# Temp_monitor.net
KiCad netlist of a schematic drawn in EAGLE
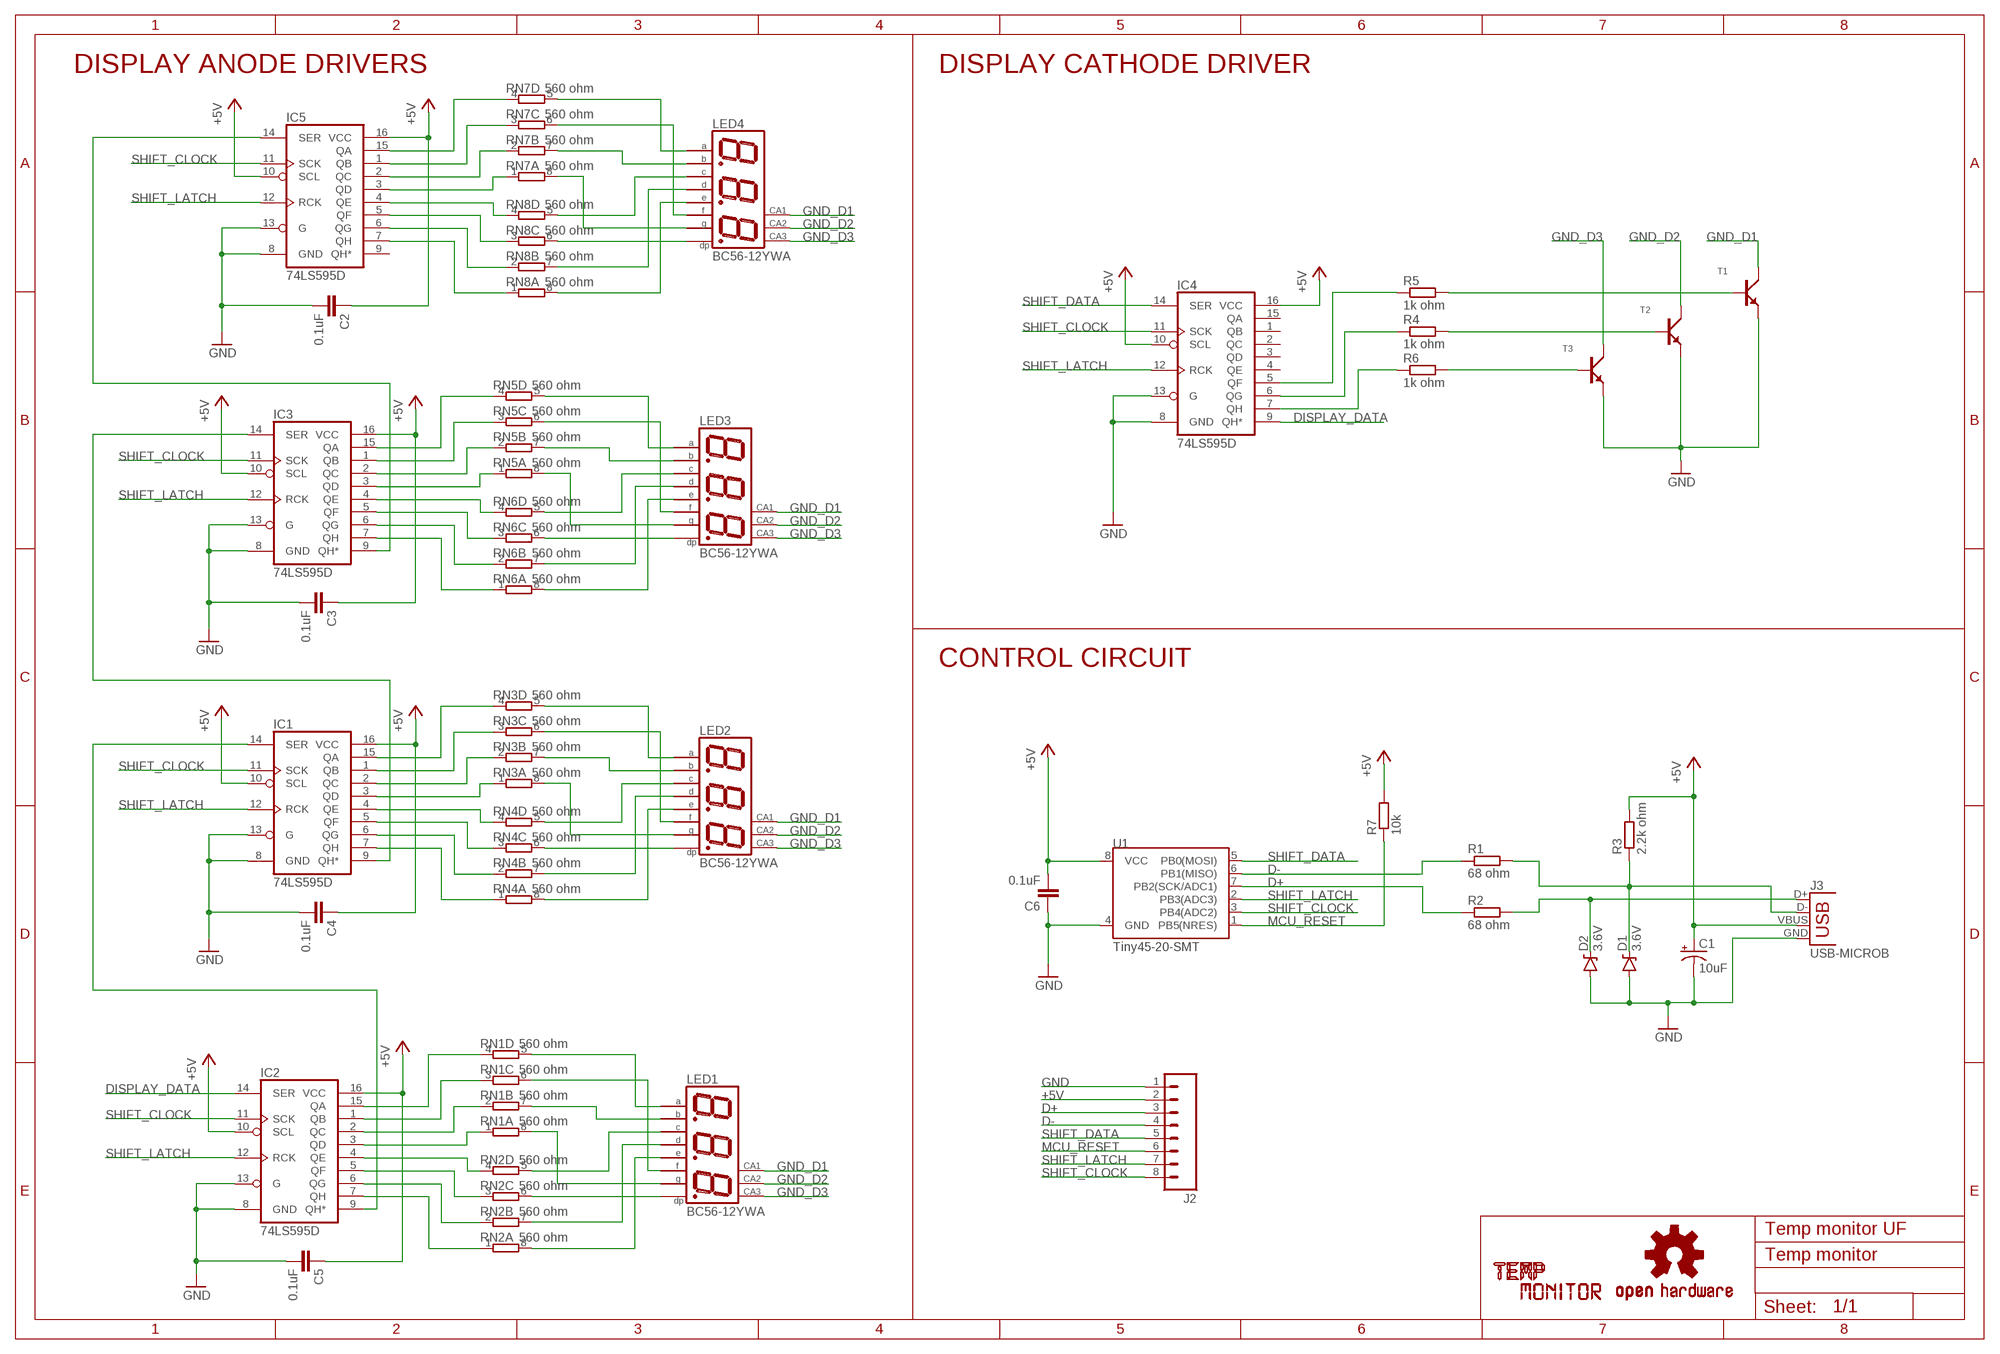
[diagram p0: schematic, sheet 1]

(export (version "E")
  (design (tool "Eeschema 10.0.6"))
  (components
    (comp (ref "C1")
      (value "10uF")
      (footprint "eagle-import:NIPPON_F80")
      (libsource (lib "eagle-import") (part "CAP_POLF80"))
    )
    (comp (ref "C2")
      (value "0.1uF")
      (footprint "eagle-import:C0805")
      (libsource (lib "eagle-import") (part "C-EUC0805"))
    )
    (comp (ref "C3")
      (value "0.1uF")
      (footprint "eagle-import:C0805")
      (libsource (lib "eagle-import") (part "C-EUC0805"))
    )
    (comp (ref "C4")
      (value "0.1uF")
      (footprint "eagle-import:C0805")
      (libsource (lib "eagle-import") (part "C-EUC0805"))
    )
    (comp (ref "C5")
      (value "0.1uF")
      (footprint "eagle-import:C0805")
      (libsource (lib "eagle-import") (part "C-EUC0805"))
    )
    (comp (ref "C6")
      (value "0.1uF")
      (footprint "eagle-import:C0805")
      (libsource (lib "eagle-import") (part "C-EUC0805"))
    )
    (comp (ref "D1")
      (value "3.6V")
      (footprint "eagle-import:SOD-123")
      (libsource (lib "eagle-import") (part "DIODE-ZENER16V"))
    )
    (comp (ref "D2")
      (value "3.6V")
      (footprint "eagle-import:SOD-123")
      (libsource (lib "eagle-import") (part "DIODE-ZENER16V"))
    )
    (comp (ref "IC1")
      (value "74LS595D")
      (footprint "eagle-import:SO16")
      (libsource (lib "eagle-import") (part "74595DLS"))
    )
    (comp (ref "IC2")
      (value "74LS595D")
      (footprint "eagle-import:SO16")
      (libsource (lib "eagle-import") (part "74595DLS"))
    )
    (comp (ref "IC3")
      (value "74LS595D")
      (footprint "eagle-import:SO16")
      (libsource (lib "eagle-import") (part "74595DLS"))
    )
    (comp (ref "IC4")
      (value "74LS595D")
      (footprint "eagle-import:SO16")
      (libsource (lib "eagle-import") (part "74595DLS"))
    )
    (comp (ref "IC5")
      (value "74LS595D")
      (footprint "eagle-import:SO16")
      (libsource (lib "eagle-import") (part "74595DLS"))
    )
    (comp (ref "J2")
      (value "TP_8")
      (footprint "eagle-import:TP_8")
      (libsource (lib "eagle-import") (part "TP_8"))
    )
    (comp (ref "J3")
      (value "USB-MICROB")
      (footprint "eagle-import:USB-MICROB")
      (libsource (lib "eagle-import") (part "USB-MICROB"))
    )
    (comp (ref "LED1")
      (value "BC56-12YWA")
      (footprint "eagle-import:BX56-12")
      (libsource (lib "eagle-import") (part "B?56-12WACY"))
    )
    (comp (ref "LED2")
      (value "BC56-12YWA")
      (footprint "eagle-import:BX56-12")
      (libsource (lib "eagle-import") (part "B?56-12WACY"))
    )
    (comp (ref "LED3")
      (value "BC56-12YWA")
      (footprint "eagle-import:BX56-12")
      (libsource (lib "eagle-import") (part "B?56-12WACY"))
    )
    (comp (ref "LED4")
      (value "BC56-12YWA")
      (footprint "eagle-import:BX56-12")
      (libsource (lib "eagle-import") (part "B?56-12WACY"))
    )
    (comp (ref "LOGO1")
      (value "OSHW-LOGOL")
      (footprint "eagle-import:OSHW-LOGO-L")
      (libsource (lib "eagle-import") (part "OSHW-LOGOL"))
    )
    (comp (ref "R1")
      (value "68 ohm")
      (footprint "eagle-import:R0805W")
      (libsource (lib "eagle-import") (part "R-EU_R0805W"))
    )
    (comp (ref "R2")
      (value "68 ohm")
      (footprint "eagle-import:R0805W")
      (libsource (lib "eagle-import") (part "R-EU_R0805W"))
    )
    (comp (ref "R3")
      (value "2.2k ohm")
      (footprint "eagle-import:R0805W")
      (libsource (lib "eagle-import") (part "R-EU_R0805W"))
    )
    (comp (ref "R4")
      (value "1k ohm")
      (footprint "eagle-import:R0805W")
      (libsource (lib "eagle-import") (part "R-EU_R0805W"))
    )
    (comp (ref "R5")
      (value "1k ohm")
      (footprint "eagle-import:R0805W")
      (libsource (lib "eagle-import") (part "R-EU_R0805W"))
    )
    (comp (ref "R6")
      (value "1k ohm")
      (footprint "eagle-import:R0805W")
      (libsource (lib "eagle-import") (part "R-EU_R0805W"))
    )
    (comp (ref "R7")
      (value "10k")
      (footprint "eagle-import:R0805W")
      (libsource (lib "eagle-import") (part "R-EU_R0805W"))
    )
    (comp (ref "RN1")
      (value "560 ohm")
      (footprint "eagle-import:EXBV8V")
      (libsource (lib "eagle-import") (part "4R-NEXBV8V"))
    )
    (comp (ref "RN2")
      (value "560 ohm")
      (footprint "eagle-import:EXBV8V")
      (libsource (lib "eagle-import") (part "4R-NEXBV8V"))
    )
    (comp (ref "RN3")
      (value "560 ohm")
      (footprint "eagle-import:EXBV8V")
      (libsource (lib "eagle-import") (part "4R-NEXBV8V"))
    )
    (comp (ref "RN4")
      (value "560 ohm")
      (footprint "eagle-import:EXBV8V")
      (libsource (lib "eagle-import") (part "4R-NEXBV8V"))
    )
    (comp (ref "RN5")
      (value "560 ohm")
      (footprint "eagle-import:EXBV8V")
      (libsource (lib "eagle-import") (part "4R-NEXBV8V"))
    )
    (comp (ref "RN6")
      (value "560 ohm")
      (footprint "eagle-import:EXBV8V")
      (libsource (lib "eagle-import") (part "4R-NEXBV8V"))
    )
    (comp (ref "RN7")
      (value "560 ohm")
      (footprint "eagle-import:EXBV8V")
      (libsource (lib "eagle-import") (part "4R-NEXBV8V"))
    )
    (comp (ref "RN8")
      (value "560 ohm")
      (footprint "eagle-import:EXBV8V")
      (libsource (lib "eagle-import") (part "4R-NEXBV8V"))
    )
    (comp (ref "T1")
      (value "NPN")
      (footprint "eagle-import:SOT23")
      (libsource (lib "eagle-import") (part "NPN"))
    )
    (comp (ref "T2")
      (value "NPN")
      (footprint "eagle-import:SOT23")
      (libsource (lib "eagle-import") (part "NPN"))
    )
    (comp (ref "T3")
      (value "NPN")
      (footprint "eagle-import:SOT23")
      (libsource (lib "eagle-import") (part "NPN"))
    )
    (comp (ref "U$1")
      (value "LOGO")
      (footprint "eagle-import:LOGO_M")
      (libsource (lib "eagle-import") (part "LOGO"))
    )
    (comp (ref "U$2")
      (value "LOGO")
      (footprint "eagle-import:LOGO_M")
      (libsource (lib "eagle-import") (part "LOGO"))
    )
    (comp (ref "U1")
      (value "Tiny45-20-SMT")
      (footprint "eagle-import:SO08-EIAJ")
      (libsource (lib "eagle-import") (part "ATTINY45TINY45-20-SMT"))
    )
  )
  (nets
    (net (code "1") (name "+5V") (class "Default")
      (node (ref "C1") (pin "+") (pinfunction "+_+") (pintype "passive"))
      (node (ref "C2") (pin "1") (pinfunction "1_1") (pintype "passive"))
      (node (ref "C3") (pin "1") (pinfunction "1_1") (pintype "passive"))
      (node (ref "C4") (pin "1") (pinfunction "1_1") (pintype "passive"))
      (node (ref "C5") (pin "1") (pinfunction "1_1") (pintype "passive"))
      (node (ref "C6") (pin "2") (pinfunction "2_2") (pintype "passive"))
      (node (ref "IC1") (pin "10") (pinfunction "SCL_10") (pintype "input"))
      (node (ref "IC1") (pin "16") (pinfunction "VCC_16") (pintype "power_in"))
      (node (ref "IC2") (pin "10") (pinfunction "SCL_10") (pintype "input"))
      (node (ref "IC2") (pin "16") (pinfunction "VCC_16") (pintype "power_in"))
      (node (ref "IC3") (pin "10") (pinfunction "SCL_10") (pintype "input"))
      (node (ref "IC3") (pin "16") (pinfunction "VCC_16") (pintype "power_in"))
      (node (ref "IC4") (pin "10") (pinfunction "SCL_10") (pintype "input"))
      (node (ref "IC4") (pin "16") (pinfunction "VCC_16") (pintype "power_in"))
      (node (ref "IC5") (pin "10") (pinfunction "SCL_10") (pintype "input"))
      (node (ref "IC5") (pin "16") (pinfunction "VCC_16") (pintype "power_in"))
      (node (ref "J2") (pin "2") (pinfunction "2_2") (pintype "passive"))
      (node (ref "J3") (pin "VBUS") (pinfunction "VBUS_VBUS") (pintype "bidirectional"))
      (node (ref "R3") (pin "2") (pinfunction "2_2") (pintype "passive"))
      (node (ref "R7") (pin "2") (pinfunction "2_2") (pintype "passive"))
      (node (ref "U1") (pin "8") (pinfunction "VCC_8") (pintype "bidirectional"))
    )
    (net (code "2") (name "/D+") (class "Default")
      (node (ref "J2") (pin "3") (pinfunction "3_3") (pintype "passive"))
      (node (ref "R2") (pin "1") (pinfunction "1_1") (pintype "passive"))
      (node (ref "U1") (pin "7") (pinfunction "PB2(SCK/ADC1)_7") (pintype "bidirectional"))
    )
    (net (code "3") (name "/D-") (class "Default")
      (node (ref "J2") (pin "4") (pinfunction "4_4") (pintype "passive"))
      (node (ref "R1") (pin "1") (pinfunction "1_1") (pintype "passive"))
      (node (ref "U1") (pin "6") (pinfunction "PB1(MISO)_6") (pintype "bidirectional"))
    )
    (net (code "4") (name "/DISPLAY_DATA") (class "Default")
      (node (ref "IC2") (pin "14") (pinfunction "SER_14") (pintype "input"))
      (node (ref "IC4") (pin "9") (pinfunction "QH*_9") (pintype "tri_state"))
    )
    (net (code "5") (name "/GND_D1") (class "Default")
      (node (ref "LED1") (pin "12") (pinfunction "CA_12") (pintype "passive"))
      (node (ref "LED2") (pin "12") (pinfunction "CA_12") (pintype "passive"))
      (node (ref "LED3") (pin "12") (pinfunction "CA_12") (pintype "passive"))
      (node (ref "LED4") (pin "12") (pinfunction "CA_12") (pintype "passive"))
      (node (ref "T1") (pin "3") (pinfunction "C_3") (pintype "bidirectional"))
    )
    (net (code "6") (name "/GND_D2") (class "Default")
      (node (ref "LED1") (pin "9") (pinfunction "CA_9") (pintype "passive"))
      (node (ref "LED2") (pin "9") (pinfunction "CA_9") (pintype "passive"))
      (node (ref "LED3") (pin "9") (pinfunction "CA_9") (pintype "passive"))
      (node (ref "LED4") (pin "9") (pinfunction "CA_9") (pintype "passive"))
      (node (ref "T2") (pin "3") (pinfunction "C_3") (pintype "bidirectional"))
    )
    (net (code "7") (name "/GND_D3") (class "Default")
      (node (ref "LED1") (pin "8") (pinfunction "CA_8") (pintype "passive"))
      (node (ref "LED2") (pin "8") (pinfunction "CA_8") (pintype "passive"))
      (node (ref "LED3") (pin "8") (pinfunction "CA_8") (pintype "passive"))
      (node (ref "LED4") (pin "8") (pinfunction "CA_8") (pintype "passive"))
      (node (ref "T3") (pin "3") (pinfunction "C_3") (pintype "bidirectional"))
    )
    (net (code "8") (name "/MCU_RESET") (class "Default")
      (node (ref "J2") (pin "6") (pinfunction "6_6") (pintype "passive"))
      (node (ref "R7") (pin "1") (pinfunction "1_1") (pintype "passive"))
      (node (ref "U1") (pin "1") (pinfunction "PB5(NRES)_1") (pintype "bidirectional"))
    )
    (net (code "9") (name "/SHIFT_CLOCK") (class "Default")
      (node (ref "IC1") (pin "11") (pinfunction "SCK_11") (pintype "input"))
      (node (ref "IC2") (pin "11") (pinfunction "SCK_11") (pintype "input"))
      (node (ref "IC3") (pin "11") (pinfunction "SCK_11") (pintype "input"))
      (node (ref "IC4") (pin "11") (pinfunction "SCK_11") (pintype "input"))
      (node (ref "IC5") (pin "11") (pinfunction "SCK_11") (pintype "input"))
      (node (ref "J2") (pin "8") (pinfunction "8_8") (pintype "passive"))
      (node (ref "U1") (pin "3") (pinfunction "PB4(ADC2)_3") (pintype "bidirectional"))
    )
    (net (code "10") (name "/SHIFT_DATA") (class "Default")
      (node (ref "IC4") (pin "14") (pinfunction "SER_14") (pintype "input"))
      (node (ref "J2") (pin "5") (pinfunction "5_5") (pintype "passive"))
      (node (ref "U1") (pin "5") (pinfunction "PB0(MOSI)_5") (pintype "bidirectional"))
    )
    (net (code "11") (name "/SHIFT_LATCH") (class "Default")
      (node (ref "IC1") (pin "12") (pinfunction "RCK_12") (pintype "input"))
      (node (ref "IC2") (pin "12") (pinfunction "RCK_12") (pintype "input"))
      (node (ref "IC3") (pin "12") (pinfunction "RCK_12") (pintype "input"))
      (node (ref "IC4") (pin "12") (pinfunction "RCK_12") (pintype "input"))
      (node (ref "IC5") (pin "12") (pinfunction "RCK_12") (pintype "input"))
      (node (ref "J2") (pin "7") (pinfunction "7_7") (pintype "passive"))
      (node (ref "U1") (pin "2") (pinfunction "PB3(ADC3)_2") (pintype "bidirectional"))
    )
    (net (code "12") (name "GND") (class "Default")
      (node (ref "C1") (pin "-") (pinfunction "-_-") (pintype "passive"))
      (node (ref "C2") (pin "2") (pinfunction "2_2") (pintype "passive"))
      (node (ref "C3") (pin "2") (pinfunction "2_2") (pintype "passive"))
      (node (ref "C4") (pin "2") (pinfunction "2_2") (pintype "passive"))
      (node (ref "C5") (pin "2") (pinfunction "2_2") (pintype "passive"))
      (node (ref "C6") (pin "1") (pinfunction "1_1") (pintype "passive"))
      (node (ref "D1") (pin "A") (pinfunction "A_A") (pintype "passive"))
      (node (ref "D2") (pin "A") (pinfunction "A_A") (pintype "passive"))
      (node (ref "IC1") (pin "13") (pinfunction "G_13") (pintype "input"))
      (node (ref "IC1") (pin "8") (pinfunction "GND_8") (pintype "power_in"))
      (node (ref "IC2") (pin "13") (pinfunction "G_13") (pintype "input"))
      (node (ref "IC2") (pin "8") (pinfunction "GND_8") (pintype "power_in"))
      (node (ref "IC3") (pin "13") (pinfunction "G_13") (pintype "input"))
      (node (ref "IC3") (pin "8") (pinfunction "GND_8") (pintype "power_in"))
      (node (ref "IC4") (pin "13") (pinfunction "G_13") (pintype "input"))
      (node (ref "IC4") (pin "8") (pinfunction "GND_8") (pintype "power_in"))
      (node (ref "IC5") (pin "13") (pinfunction "G_13") (pintype "input"))
      (node (ref "IC5") (pin "8") (pinfunction "GND_8") (pintype "power_in"))
      (node (ref "J2") (pin "1") (pinfunction "1_1") (pintype "passive"))
      (node (ref "J3") (pin "GND") (pinfunction "GND_GND") (pintype "bidirectional"))
      (node (ref "T1") (pin "2") (pinfunction "E_2") (pintype "bidirectional"))
      (node (ref "T2") (pin "2") (pinfunction "E_2") (pintype "bidirectional"))
      (node (ref "T3") (pin "2") (pinfunction "E_2") (pintype "bidirectional"))
      (node (ref "U1") (pin "4") (pinfunction "GND_4") (pintype "bidirectional"))
    )
    (net (code "13") (name "Net-(D1-PadC)") (class "Default")
      (node (ref "D1") (pin "C") (pinfunction "C_C") (pintype "passive"))
      (node (ref "J3") (pin "D-") (pinfunction "D-_D-") (pintype "bidirectional"))
      (node (ref "R1") (pin "2") (pinfunction "2_2") (pintype "passive"))
      (node (ref "R3") (pin "1") (pinfunction "1_1") (pintype "passive"))
    )
    (net (code "14") (name "Net-(D2-PadC)") (class "Default")
      (node (ref "D2") (pin "C") (pinfunction "C_C") (pintype "passive"))
      (node (ref "J3") (pin "D+") (pinfunction "D+_D+") (pintype "bidirectional"))
      (node (ref "R2") (pin "2") (pinfunction "2_2") (pintype "passive"))
    )
    (net (code "15") (name "Net-(IC1-QA)") (class "Default")
      (node (ref "IC1") (pin "15") (pinfunction "QA_15") (pintype "tri_state"))
      (node (ref "RN3") (pin "4") (pinfunction "1_4") (pintype "passive"))
    )
    (net (code "16") (name "Net-(IC1-QB)") (class "Default")
      (node (ref "IC1") (pin "1") (pinfunction "QB_1") (pintype "tri_state"))
      (node (ref "RN3") (pin "3") (pinfunction "1_3") (pintype "passive"))
    )
    (net (code "17") (name "Net-(IC1-QC)") (class "Default")
      (node (ref "IC1") (pin "2") (pinfunction "QC_2") (pintype "tri_state"))
      (node (ref "RN3") (pin "2") (pinfunction "1_2") (pintype "passive"))
    )
    (net (code "18") (name "Net-(IC1-QD)") (class "Default")
      (node (ref "IC1") (pin "3") (pinfunction "QD_3") (pintype "tri_state"))
      (node (ref "RN3") (pin "1") (pinfunction "1_1") (pintype "passive"))
    )
    (net (code "19") (name "Net-(IC1-QE)") (class "Default")
      (node (ref "IC1") (pin "4") (pinfunction "QE_4") (pintype "tri_state"))
      (node (ref "RN4") (pin "4") (pinfunction "1_4") (pintype "passive"))
    )
    (net (code "20") (name "Net-(IC1-QF)") (class "Default")
      (node (ref "IC1") (pin "5") (pinfunction "QF_5") (pintype "tri_state"))
      (node (ref "RN4") (pin "3") (pinfunction "1_3") (pintype "passive"))
    )
    (net (code "21") (name "Net-(IC1-QG)") (class "Default")
      (node (ref "IC1") (pin "6") (pinfunction "QG_6") (pintype "tri_state"))
      (node (ref "RN4") (pin "2") (pinfunction "1_2") (pintype "passive"))
    )
    (net (code "22") (name "Net-(IC1-QH)") (class "Default")
      (node (ref "IC1") (pin "7") (pinfunction "QH_7") (pintype "tri_state"))
      (node (ref "RN4") (pin "1") (pinfunction "1_1") (pintype "passive"))
    )
    (net (code "23") (name "Net-(IC1-QH*)") (class "Default")
      (node (ref "IC1") (pin "9") (pinfunction "QH*_9") (pintype "tri_state"))
      (node (ref "IC3") (pin "14") (pinfunction "SER_14") (pintype "input"))
    )
    (net (code "24") (name "Net-(IC1-SER)") (class "Default")
      (node (ref "IC1") (pin "14") (pinfunction "SER_14") (pintype "input"))
      (node (ref "IC2") (pin "9") (pinfunction "QH*_9") (pintype "tri_state"))
    )
    (net (code "25") (name "Net-(IC2-QA)") (class "Default")
      (node (ref "IC2") (pin "15") (pinfunction "QA_15") (pintype "tri_state"))
      (node (ref "RN1") (pin "4") (pinfunction "1_4") (pintype "passive"))
    )
    (net (code "26") (name "Net-(IC2-QB)") (class "Default")
      (node (ref "IC2") (pin "1") (pinfunction "QB_1") (pintype "tri_state"))
      (node (ref "RN1") (pin "3") (pinfunction "1_3") (pintype "passive"))
    )
    (net (code "27") (name "Net-(IC2-QC)") (class "Default")
      (node (ref "IC2") (pin "2") (pinfunction "QC_2") (pintype "tri_state"))
      (node (ref "RN1") (pin "2") (pinfunction "1_2") (pintype "passive"))
    )
    (net (code "28") (name "Net-(IC2-QD)") (class "Default")
      (node (ref "IC2") (pin "3") (pinfunction "QD_3") (pintype "tri_state"))
      (node (ref "RN1") (pin "1") (pinfunction "1_1") (pintype "passive"))
    )
    (net (code "29") (name "Net-(IC2-QE)") (class "Default")
      (node (ref "IC2") (pin "4") (pinfunction "QE_4") (pintype "tri_state"))
      (node (ref "RN2") (pin "4") (pinfunction "1_4") (pintype "passive"))
    )
    (net (code "30") (name "Net-(IC2-QF)") (class "Default")
      (node (ref "IC2") (pin "5") (pinfunction "QF_5") (pintype "tri_state"))
      (node (ref "RN2") (pin "3") (pinfunction "1_3") (pintype "passive"))
    )
    (net (code "31") (name "Net-(IC2-QG)") (class "Default")
      (node (ref "IC2") (pin "6") (pinfunction "QG_6") (pintype "tri_state"))
      (node (ref "RN2") (pin "2") (pinfunction "1_2") (pintype "passive"))
    )
    (net (code "32") (name "Net-(IC2-QH)") (class "Default")
      (node (ref "IC2") (pin "7") (pinfunction "QH_7") (pintype "tri_state"))
      (node (ref "RN2") (pin "1") (pinfunction "1_1") (pintype "passive"))
    )
    (net (code "33") (name "Net-(IC3-QA)") (class "Default")
      (node (ref "IC3") (pin "15") (pinfunction "QA_15") (pintype "tri_state"))
      (node (ref "RN5") (pin "4") (pinfunction "1_4") (pintype "passive"))
    )
    (net (code "34") (name "Net-(IC3-QB)") (class "Default")
      (node (ref "IC3") (pin "1") (pinfunction "QB_1") (pintype "tri_state"))
      (node (ref "RN5") (pin "3") (pinfunction "1_3") (pintype "passive"))
    )
    (net (code "35") (name "Net-(IC3-QC)") (class "Default")
      (node (ref "IC3") (pin "2") (pinfunction "QC_2") (pintype "tri_state"))
      (node (ref "RN5") (pin "2") (pinfunction "1_2") (pintype "passive"))
    )
    (net (code "36") (name "Net-(IC3-QD)") (class "Default")
      (node (ref "IC3") (pin "3") (pinfunction "QD_3") (pintype "tri_state"))
      (node (ref "RN5") (pin "1") (pinfunction "1_1") (pintype "passive"))
    )
    (net (code "37") (name "Net-(IC3-QE)") (class "Default")
      (node (ref "IC3") (pin "4") (pinfunction "QE_4") (pintype "tri_state"))
      (node (ref "RN6") (pin "4") (pinfunction "1_4") (pintype "passive"))
    )
    (net (code "38") (name "Net-(IC3-QF)") (class "Default")
      (node (ref "IC3") (pin "5") (pinfunction "QF_5") (pintype "tri_state"))
      (node (ref "RN6") (pin "3") (pinfunction "1_3") (pintype "passive"))
    )
    (net (code "39") (name "Net-(IC3-QG)") (class "Default")
      (node (ref "IC3") (pin "6") (pinfunction "QG_6") (pintype "tri_state"))
      (node (ref "RN6") (pin "2") (pinfunction "1_2") (pintype "passive"))
    )
    (net (code "40") (name "Net-(IC3-QH)") (class "Default")
      (node (ref "IC3") (pin "7") (pinfunction "QH_7") (pintype "tri_state"))
      (node (ref "RN6") (pin "1") (pinfunction "1_1") (pintype "passive"))
    )
    (net (code "41") (name "Net-(IC3-QH*)") (class "Default")
      (node (ref "IC3") (pin "9") (pinfunction "QH*_9") (pintype "tri_state"))
      (node (ref "IC5") (pin "14") (pinfunction "SER_14") (pintype "input"))
    )
    (net (code "42") (name "Net-(IC4-QF)") (class "Default")
      (node (ref "IC4") (pin "5") (pinfunction "QF_5") (pintype "tri_state"))
      (node (ref "R5") (pin "1") (pinfunction "1_1") (pintype "passive"))
    )
    (net (code "43") (name "Net-(IC4-QG)") (class "Default")
      (node (ref "IC4") (pin "6") (pinfunction "QG_6") (pintype "tri_state"))
      (node (ref "R4") (pin "1") (pinfunction "1_1") (pintype "passive"))
    )
    (net (code "44") (name "Net-(IC4-QH)") (class "Default")
      (node (ref "IC4") (pin "7") (pinfunction "QH_7") (pintype "tri_state"))
      (node (ref "R6") (pin "1") (pinfunction "1_1") (pintype "passive"))
    )
    (net (code "45") (name "Net-(IC5-QA)") (class "Default")
      (node (ref "IC5") (pin "15") (pinfunction "QA_15") (pintype "tri_state"))
      (node (ref "RN7") (pin "4") (pinfunction "1_4") (pintype "passive"))
    )
    (net (code "46") (name "Net-(IC5-QB)") (class "Default")
      (node (ref "IC5") (pin "1") (pinfunction "QB_1") (pintype "tri_state"))
      (node (ref "RN7") (pin "3") (pinfunction "1_3") (pintype "passive"))
    )
    (net (code "47") (name "Net-(IC5-QC)") (class "Default")
      (node (ref "IC5") (pin "2") (pinfunction "QC_2") (pintype "tri_state"))
      (node (ref "RN7") (pin "2") (pinfunction "1_2") (pintype "passive"))
    )
    (net (code "48") (name "Net-(IC5-QD)") (class "Default")
      (node (ref "IC5") (pin "3") (pinfunction "QD_3") (pintype "tri_state"))
      (node (ref "RN7") (pin "1") (pinfunction "1_1") (pintype "passive"))
    )
    (net (code "49") (name "Net-(IC5-QE)") (class "Default")
      (node (ref "IC5") (pin "4") (pinfunction "QE_4") (pintype "tri_state"))
      (node (ref "RN8") (pin "4") (pinfunction "1_4") (pintype "passive"))
    )
    (net (code "50") (name "Net-(IC5-QF)") (class "Default")
      (node (ref "IC5") (pin "5") (pinfunction "QF_5") (pintype "tri_state"))
      (node (ref "RN8") (pin "3") (pinfunction "1_3") (pintype "passive"))
    )
    (net (code "51") (name "Net-(IC5-QG)") (class "Default")
      (node (ref "IC5") (pin "6") (pinfunction "QG_6") (pintype "tri_state"))
      (node (ref "RN8") (pin "2") (pinfunction "1_2") (pintype "passive"))
    )
    (net (code "52") (name "Net-(IC5-QH)") (class "Default")
      (node (ref "IC5") (pin "7") (pinfunction "QH_7") (pintype "tri_state"))
      (node (ref "RN8") (pin "1") (pinfunction "1_1") (pintype "passive"))
    )
    (net (code "53") (name "Net-(LED1-A)") (class "Default")
      (node (ref "LED1") (pin "11") (pinfunction "A_11") (pintype "passive"))
      (node (ref "RN1") (pin "5") (pinfunction "2_5") (pintype "passive"))
    )
    (net (code "54") (name "Net-(LED1-B)") (class "Default")
      (node (ref "LED1") (pin "7") (pinfunction "B_7") (pintype "passive"))
      (node (ref "RN1") (pin "7") (pinfunction "2_7") (pintype "passive"))
    )
    (net (code "55") (name "Net-(LED1-C)") (class "Default")
      (node (ref "LED1") (pin "4") (pinfunction "C_4") (pintype "passive"))
      (node (ref "RN2") (pin "5") (pinfunction "2_5") (pintype "passive"))
    )
    (net (code "56") (name "Net-(LED1-D)") (class "Default")
      (node (ref "LED1") (pin "2") (pinfunction "D_2") (pintype "passive"))
      (node (ref "RN2") (pin "7") (pinfunction "2_7") (pintype "passive"))
    )
    (net (code "57") (name "Net-(LED1-DP)") (class "Default")
      (node (ref "LED1") (pin "3") (pinfunction "DP_3") (pintype "passive"))
      (node (ref "RN2") (pin "6") (pinfunction "2_6") (pintype "passive"))
    )
    (net (code "58") (name "Net-(LED1-E)") (class "Default")
      (node (ref "LED1") (pin "1") (pinfunction "E_1") (pintype "passive"))
      (node (ref "RN2") (pin "8") (pinfunction "2_8") (pintype "passive"))
    )
    (net (code "59") (name "Net-(LED1-F)") (class "Default")
      (node (ref "LED1") (pin "10") (pinfunction "F_10") (pintype "passive"))
      (node (ref "RN1") (pin "6") (pinfunction "2_6") (pintype "passive"))
    )
    (net (code "60") (name "Net-(LED1-G)") (class "Default")
      (node (ref "LED1") (pin "5") (pinfunction "G_5") (pintype "passive"))
      (node (ref "RN1") (pin "8") (pinfunction "2_8") (pintype "passive"))
    )
    (net (code "61") (name "Net-(LED2-A)") (class "Default")
      (node (ref "LED2") (pin "11") (pinfunction "A_11") (pintype "passive"))
      (node (ref "RN3") (pin "5") (pinfunction "2_5") (pintype "passive"))
    )
    (net (code "62") (name "Net-(LED2-B)") (class "Default")
      (node (ref "LED2") (pin "7") (pinfunction "B_7") (pintype "passive"))
      (node (ref "RN3") (pin "7") (pinfunction "2_7") (pintype "passive"))
    )
    (net (code "63") (name "Net-(LED2-C)") (class "Default")
      (node (ref "LED2") (pin "4") (pinfunction "C_4") (pintype "passive"))
      (node (ref "RN4") (pin "5") (pinfunction "2_5") (pintype "passive"))
    )
    (net (code "64") (name "Net-(LED2-D)") (class "Default")
      (node (ref "LED2") (pin "2") (pinfunction "D_2") (pintype "passive"))
      (node (ref "RN4") (pin "7") (pinfunction "2_7") (pintype "passive"))
    )
    (net (code "65") (name "Net-(LED2-DP)") (class "Default")
      (node (ref "LED2") (pin "3") (pinfunction "DP_3") (pintype "passive"))
      (node (ref "RN4") (pin "6") (pinfunction "2_6") (pintype "passive"))
    )
    (net (code "66") (name "Net-(LED2-E)") (class "Default")
      (node (ref "LED2") (pin "1") (pinfunction "E_1") (pintype "passive"))
      (node (ref "RN4") (pin "8") (pinfunction "2_8") (pintype "passive"))
    )
    (net (code "67") (name "Net-(LED2-F)") (class "Default")
      (node (ref "LED2") (pin "10") (pinfunction "F_10") (pintype "passive"))
      (node (ref "RN3") (pin "6") (pinfunction "2_6") (pintype "passive"))
    )
    (net (code "68") (name "Net-(LED2-G)") (class "Default")
      (node (ref "LED2") (pin "5") (pinfunction "G_5") (pintype "passive"))
      (node (ref "RN3") (pin "8") (pinfunction "2_8") (pintype "passive"))
    )
    (net (code "69") (name "Net-(LED3-A)") (class "Default")
      (node (ref "LED3") (pin "11") (pinfunction "A_11") (pintype "passive"))
      (node (ref "RN5") (pin "5") (pinfunction "2_5") (pintype "passive"))
    )
    (net (code "70") (name "Net-(LED3-B)") (class "Default")
      (node (ref "LED3") (pin "7") (pinfunction "B_7") (pintype "passive"))
      (node (ref "RN5") (pin "7") (pinfunction "2_7") (pintype "passive"))
    )
    (net (code "71") (name "Net-(LED3-C)") (class "Default")
      (node (ref "LED3") (pin "4") (pinfunction "C_4") (pintype "passive"))
      (node (ref "RN6") (pin "5") (pinfunction "2_5") (pintype "passive"))
    )
    (net (code "72") (name "Net-(LED3-D)") (class "Default")
      (node (ref "LED3") (pin "2") (pinfunction "D_2") (pintype "passive"))
      (node (ref "RN6") (pin "7") (pinfunction "2_7") (pintype "passive"))
    )
    (net (code "73") (name "Net-(LED3-DP)") (class "Default")
      (node (ref "LED3") (pin "3") (pinfunction "DP_3") (pintype "passive"))
      (node (ref "RN6") (pin "6") (pinfunction "2_6") (pintype "passive"))
    )
    (net (code "74") (name "Net-(LED3-E)") (class "Default")
      (node (ref "LED3") (pin "1") (pinfunction "E_1") (pintype "passive"))
      (node (ref "RN6") (pin "8") (pinfunction "2_8") (pintype "passive"))
    )
    (net (code "75") (name "Net-(LED3-F)") (class "Default")
      (node (ref "LED3") (pin "10") (pinfunction "F_10") (pintype "passive"))
      (node (ref "RN5") (pin "6") (pinfunction "2_6") (pintype "passive"))
    )
    (net (code "76") (name "Net-(LED3-G)") (class "Default")
      (node (ref "LED3") (pin "5") (pinfunction "G_5") (pintype "passive"))
      (node (ref "RN5") (pin "8") (pinfunction "2_8") (pintype "passive"))
    )
    (net (code "77") (name "Net-(LED4-A)") (class "Default")
      (node (ref "LED4") (pin "11") (pinfunction "A_11") (pintype "passive"))
      (node (ref "RN7") (pin "5") (pinfunction "2_5") (pintype "passive"))
    )
    (net (code "78") (name "Net-(LED4-B)") (class "Default")
      (node (ref "LED4") (pin "7") (pinfunction "B_7") (pintype "passive"))
      (node (ref "RN7") (pin "7") (pinfunction "2_7") (pintype "passive"))
    )
    (net (code "79") (name "Net-(LED4-C)") (class "Default")
      (node (ref "LED4") (pin "4") (pinfunction "C_4") (pintype "passive"))
      (node (ref "RN8") (pin "5") (pinfunction "2_5") (pintype "passive"))
    )
    (net (code "80") (name "Net-(LED4-D)") (class "Default")
      (node (ref "LED4") (pin "2") (pinfunction "D_2") (pintype "passive"))
      (node (ref "RN8") (pin "7") (pinfunction "2_7") (pintype "passive"))
    )
    (net (code "81") (name "Net-(LED4-DP)") (class "Default")
      (node (ref "LED4") (pin "3") (pinfunction "DP_3") (pintype "passive"))
      (node (ref "RN8") (pin "6") (pinfunction "2_6") (pintype "passive"))
    )
    (net (code "82") (name "Net-(LED4-E)") (class "Default")
      (node (ref "LED4") (pin "1") (pinfunction "E_1") (pintype "passive"))
      (node (ref "RN8") (pin "8") (pinfunction "2_8") (pintype "passive"))
    )
    (net (code "83") (name "Net-(LED4-F)") (class "Default")
      (node (ref "LED4") (pin "10") (pinfunction "F_10") (pintype "passive"))
      (node (ref "RN7") (pin "6") (pinfunction "2_6") (pintype "passive"))
    )
    (net (code "84") (name "Net-(LED4-G)") (class "Default")
      (node (ref "LED4") (pin "5") (pinfunction "G_5") (pintype "passive"))
      (node (ref "RN7") (pin "8") (pinfunction "2_8") (pintype "passive"))
    )
    (net (code "85") (name "Net-(T1-B)") (class "Default")
      (node (ref "R5") (pin "2") (pinfunction "2_2") (pintype "passive"))
      (node (ref "T1") (pin "1") (pinfunction "B_1") (pintype "bidirectional"))
    )
    (net (code "86") (name "Net-(T2-B)") (class "Default")
      (node (ref "R4") (pin "2") (pinfunction "2_2") (pintype "passive"))
      (node (ref "T2") (pin "1") (pinfunction "B_1") (pintype "bidirectional"))
    )
    (net (code "87") (name "Net-(T3-B)") (class "Default")
      (node (ref "R6") (pin "2") (pinfunction "2_2") (pintype "passive"))
      (node (ref "T3") (pin "1") (pinfunction "B_1") (pintype "bidirectional"))
    )
    (net (code "88") (name "unconnected-(IC4-QA-Pad15)") (class "Default")
      (node (ref "IC4") (pin "15") (pinfunction "QA_15") (pintype "tri_state"))
    )
    (net (code "89") (name "unconnected-(IC4-QB-Pad1)") (class "Default")
      (node (ref "IC4") (pin "1") (pinfunction "QB_1") (pintype "tri_state"))
    )
    (net (code "90") (name "unconnected-(IC4-QC-Pad2)") (class "Default")
      (node (ref "IC4") (pin "2") (pinfunction "QC_2") (pintype "tri_state"))
    )
    (net (code "91") (name "unconnected-(IC4-QD-Pad3)") (class "Default")
      (node (ref "IC4") (pin "3") (pinfunction "QD_3") (pintype "tri_state"))
    )
    (net (code "92") (name "unconnected-(IC4-QE-Pad4)") (class "Default")
      (node (ref "IC4") (pin "4") (pinfunction "QE_4") (pintype "tri_state"))
    )
    (net (code "93") (name "unconnected-(IC5-QH*-Pad9)") (class "Default")
      (node (ref "IC5") (pin "9") (pinfunction "QH*_9") (pintype "tri_state"))
    )
  )
)
